# WiFi_UART_Board_R1.net
KiCad netlist of a schematic drawn in EAGLE
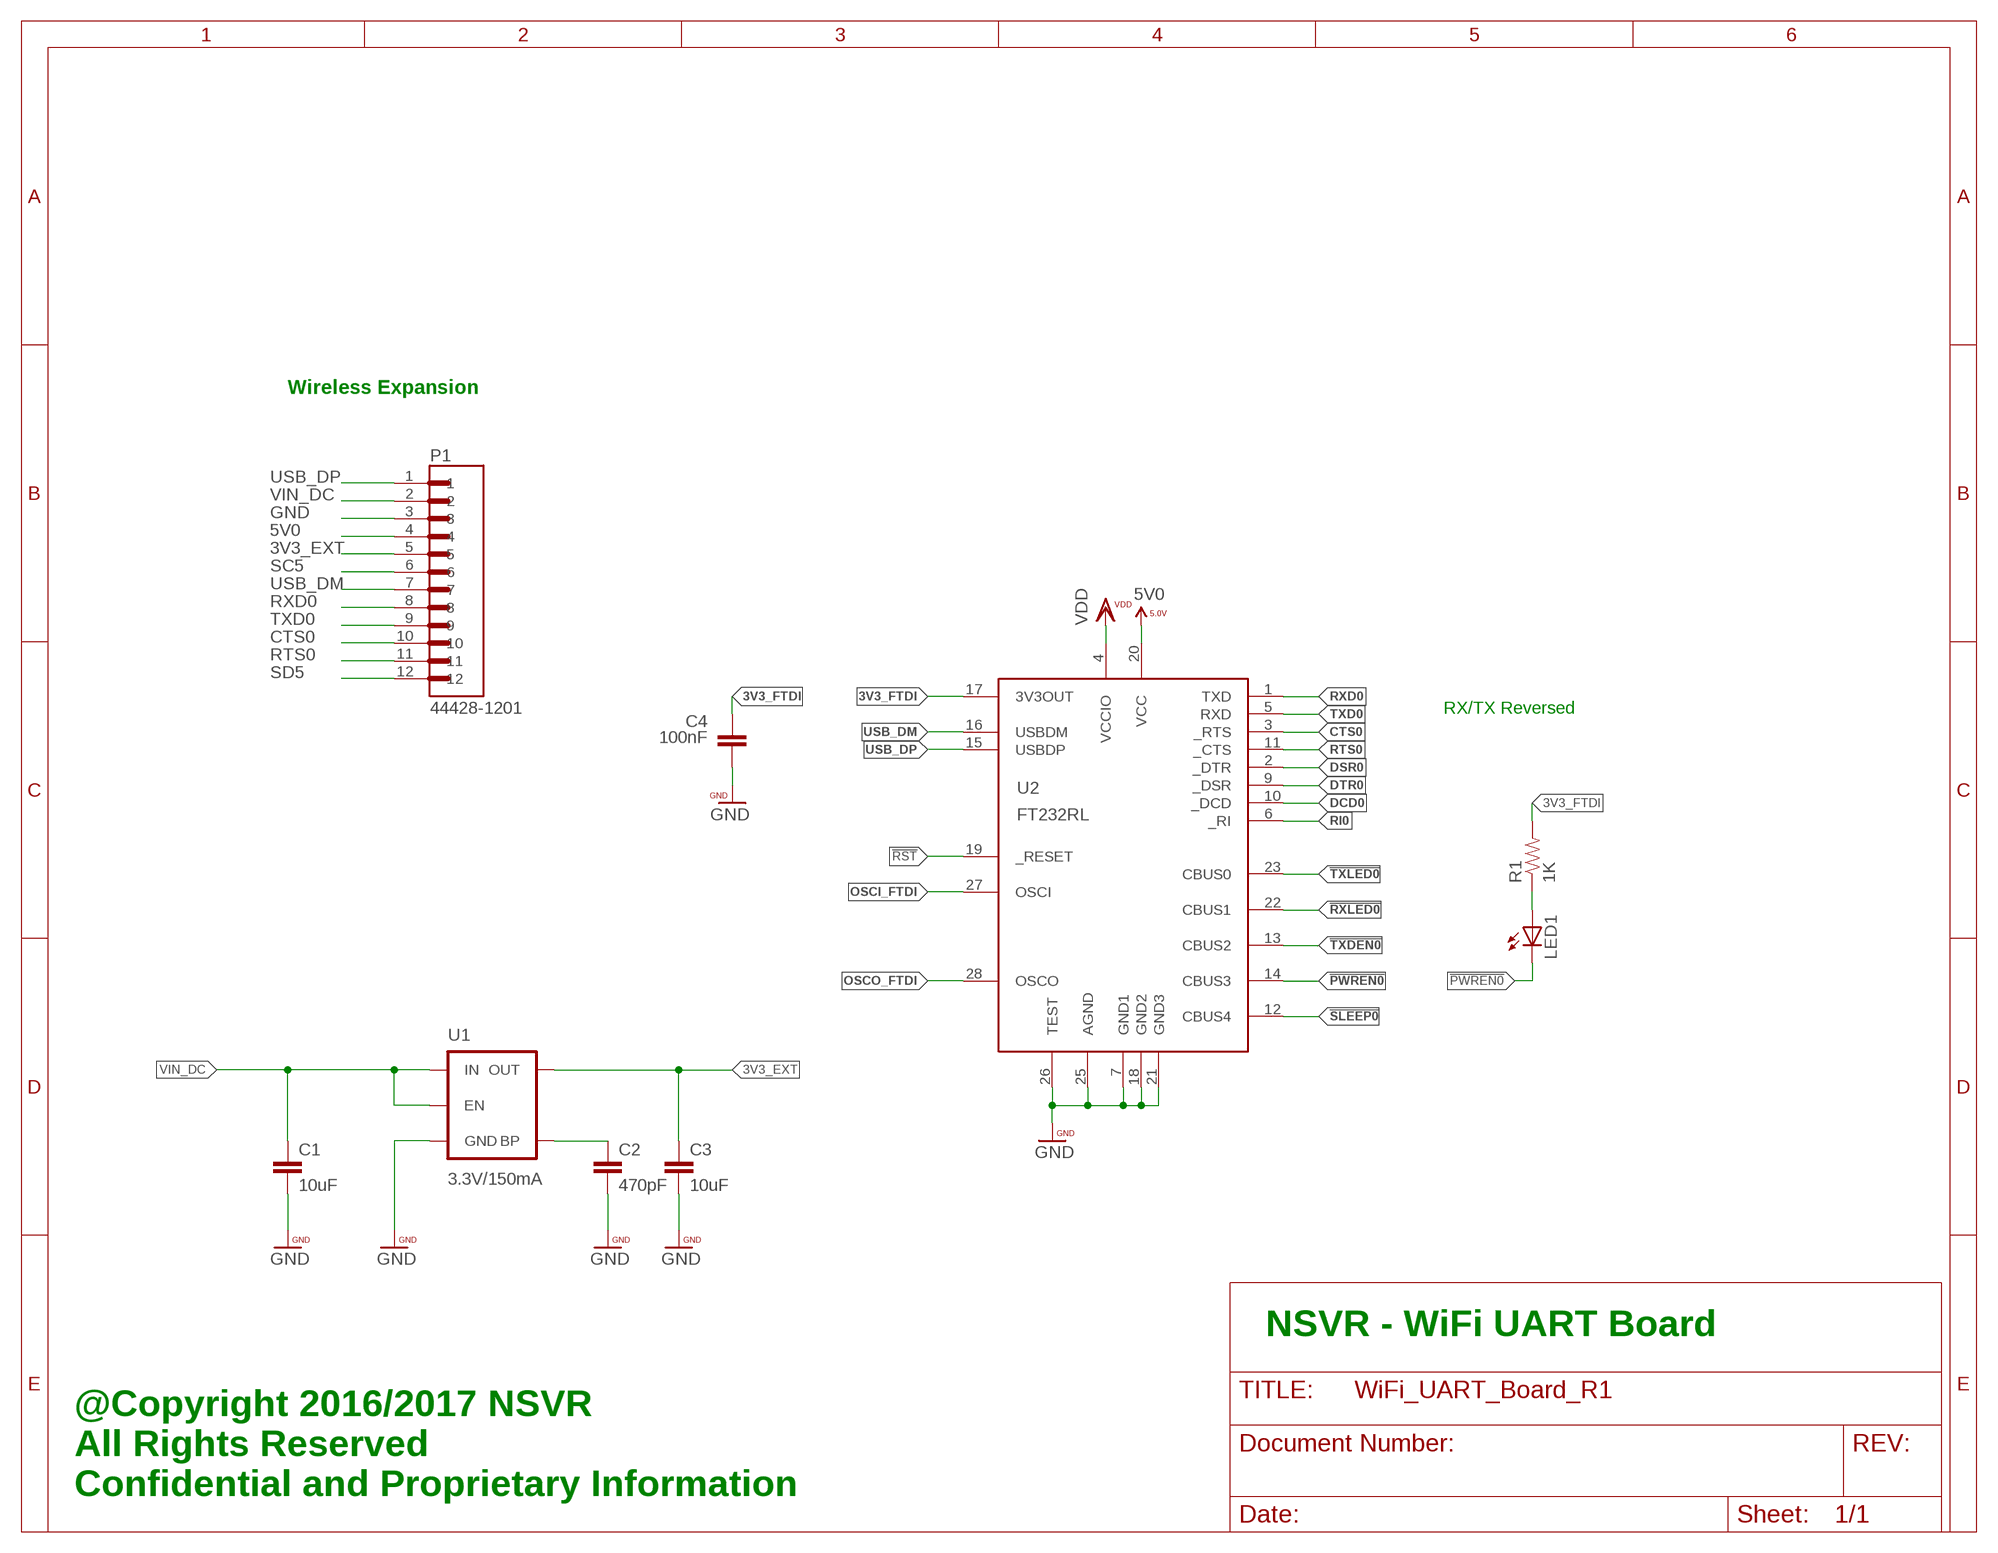
[diagram p0: schematic, sheet 1]

(export (version "E")
  (design (tool "Eeschema 10.0.6"))
  (components
    (comp (ref "C1")
      (value "10uF")
      (footprint "eagle-import:0603-CAP")
      (libsource (lib "eagle-import") (part "CAP0603-CAP"))
    )
    (comp (ref "C2")
      (value "470pF")
      (footprint "eagle-import:0402-CAP")
      (libsource (lib "eagle-import") (part "CAP0402-CAP"))
    )
    (comp (ref "C3")
      (value "10uF")
      (footprint "eagle-import:0603-CAP")
      (libsource (lib "eagle-import") (part "CAP0603-CAP"))
    )
    (comp (ref "C4")
      (value "100nF")
      (footprint "eagle-import:0402-CAP")
      (libsource (lib "eagle-import") (part "CAP0402-CAP"))
    )
    (comp (ref "LED1")
      (value "LEDCHIP-LED0603")
      (footprint "eagle-import:CHIP-LED0603")
      (libsource (lib "eagle-import") (part "LEDCHIP-LED0603"))
    )
    (comp (ref "P1")
      (value "44428-1201")
      (footprint "eagle-import:MOLEX_44428-1201")
      (fields (field (name "MF") "Molex"))
      (libsource (lib "eagle-import") (part "44428-1201"))
    )
    (comp (ref "R1")
      (value "1K")
      (footprint "eagle-import:EIA-0402")
      (libsource (lib "eagle-import") (part "RESISTOR0402-TYP"))
    )
    (comp (ref "U1")
      (value "3.3V/150mA")
      (footprint "eagle-import:SOT23-5")
      (libsource (lib "eagle-import") (part "V_REG_MIC52053.3V"))
    )
    (comp (ref "U2")
      (value "FT232RL")
      (footprint "eagle-import:SSOP28DB")
      (libsource (lib "eagle-import") (part "FT232RL"))
    )
  )
  (nets
    (net (code "1") (name "/SC5") (class "Default")
      (node (ref "P1") (pin "6") (pinfunction "6_6") (pintype "passive"))
    )
    (net (code "2") (name "/SD5") (class "Default")
      (node (ref "P1") (pin "12") (pinfunction "12_12") (pintype "passive"))
    )
    (net (code "3") (name "/~{PWREN0}") (class "Default")
      (node (ref "LED1") (pin "C") (pinfunction "C_C") (pintype "passive"))
      (node (ref "U2") (pin "14") (pinfunction "CBUS3_14") (pintype "bidirectional"))
    )
    (net (code "4") (name "/~{RST}") (class "Default")
      (node (ref "U2") (pin "19") (pinfunction "_RESET_19") (pintype "input"))
    )
    (net (code "5") (name "/~{RXLED0}") (class "Default")
      (node (ref "U2") (pin "22") (pinfunction "CBUS1_22") (pintype "bidirectional"))
    )
    (net (code "6") (name "/~{SLEEP0}") (class "Default")
      (node (ref "U2") (pin "12") (pinfunction "CBUS4_12") (pintype "bidirectional"))
    )
    (net (code "7") (name "/~{TXDEN0}") (class "Default")
      (node (ref "U2") (pin "13") (pinfunction "CBUS2_13") (pintype "bidirectional"))
    )
    (net (code "8") (name "/~{TXLED0}") (class "Default")
      (node (ref "U2") (pin "23") (pinfunction "CBUS0_23") (pintype "bidirectional"))
    )
    (net (code "9") (name "3V3_EXT") (class "Default")
      (node (ref "C3") (pin "1") (pinfunction "1_1") (pintype "passive"))
      (node (ref "P1") (pin "5") (pinfunction "5_5") (pintype "passive"))
      (node (ref "U1") (pin "5") (pinfunction "OUT_5") (pintype "passive"))
    )
    (net (code "10") (name "3V3_FTDI") (class "Default")
      (node (ref "C4") (pin "1") (pinfunction "1_1") (pintype "passive"))
      (node (ref "R1") (pin "2") (pinfunction "2_2") (pintype "passive"))
      (node (ref "U2") (pin "17") (pinfunction "3V3OUT_17") (pintype "output"))
    )
    (net (code "11") (name "5V0") (class "Default")
      (node (ref "P1") (pin "4") (pinfunction "4_4") (pintype "passive"))
      (node (ref "U2") (pin "20") (pinfunction "VCC_20") (pintype "power_in"))
    )
    (net (code "12") (name "CTS0") (class "Default")
      (node (ref "P1") (pin "10") (pinfunction "10_10") (pintype "passive"))
      (node (ref "U2") (pin "3") (pinfunction "_RTS_3") (pintype "output"))
    )
    (net (code "13") (name "DCD0") (class "Default")
      (node (ref "U2") (pin "10") (pinfunction "_DCD_10") (pintype "input"))
    )
    (net (code "14") (name "DSR0") (class "Default")
      (node (ref "U2") (pin "2") (pinfunction "_DTR_2") (pintype "output"))
    )
    (net (code "15") (name "DTR0") (class "Default")
      (node (ref "U2") (pin "9") (pinfunction "_DSR_9") (pintype "input"))
    )
    (net (code "16") (name "GND") (class "Default")
      (node (ref "C1") (pin "2") (pinfunction "2_2") (pintype "passive"))
      (node (ref "C2") (pin "2") (pinfunction "2_2") (pintype "passive"))
      (node (ref "C3") (pin "2") (pinfunction "2_2") (pintype "passive"))
      (node (ref "C4") (pin "2") (pinfunction "2_2") (pintype "passive"))
      (node (ref "P1") (pin "3") (pinfunction "3_3") (pintype "passive"))
      (node (ref "U1") (pin "2") (pinfunction "GND_2") (pintype "input"))
      (node (ref "U2") (pin "18") (pinfunction "GND2_18") (pintype "power_in"))
      (node (ref "U2") (pin "21") (pinfunction "GND3_21") (pintype "power_in"))
      (node (ref "U2") (pin "25") (pinfunction "AGND_25") (pintype "power_in"))
      (node (ref "U2") (pin "26") (pinfunction "TEST_26") (pintype "input"))
      (node (ref "U2") (pin "7") (pinfunction "GND1_7") (pintype "power_in"))
    )
    (net (code "17") (name "Net-(LED1-PadA)") (class "Default")
      (node (ref "LED1") (pin "A") (pinfunction "A_A") (pintype "passive"))
      (node (ref "R1") (pin "1") (pinfunction "1_1") (pintype "passive"))
    )
    (net (code "18") (name "Net-(U1-BP)") (class "Default")
      (node (ref "C2") (pin "1") (pinfunction "1_1") (pintype "passive"))
      (node (ref "U1") (pin "4") (pinfunction "BP_4") (pintype "input"))
    )
    (net (code "19") (name "OSCI_FTDI") (class "Default")
      (node (ref "U2") (pin "27") (pinfunction "OSCI_27") (pintype "input"))
    )
    (net (code "20") (name "OSCO_FTDI") (class "Default")
      (node (ref "U2") (pin "28") (pinfunction "OSCO_28") (pintype "output"))
    )
    (net (code "21") (name "RI0") (class "Default")
      (node (ref "U2") (pin "6") (pinfunction "_RI_6") (pintype "input"))
    )
    (net (code "22") (name "RTS0") (class "Default")
      (node (ref "P1") (pin "11") (pinfunction "11_11") (pintype "passive"))
      (node (ref "U2") (pin "11") (pinfunction "_CTS_11") (pintype "input"))
    )
    (net (code "23") (name "RXD0") (class "Default")
      (node (ref "P1") (pin "8") (pinfunction "8_8") (pintype "passive"))
      (node (ref "U2") (pin "1") (pinfunction "TXD_1") (pintype "output"))
    )
    (net (code "24") (name "TXD0") (class "Default")
      (node (ref "P1") (pin "9") (pinfunction "9_9") (pintype "passive"))
      (node (ref "U2") (pin "5") (pinfunction "RXD_5") (pintype "input"))
    )
    (net (code "25") (name "USB_DM") (class "Default")
      (node (ref "P1") (pin "7") (pinfunction "7_7") (pintype "passive"))
      (node (ref "U2") (pin "16") (pinfunction "USBDM_16") (pintype "bidirectional"))
    )
    (net (code "26") (name "USB_DP") (class "Default")
      (node (ref "P1") (pin "1") (pinfunction "1_1") (pintype "passive"))
      (node (ref "U2") (pin "15") (pinfunction "USBDP_15") (pintype "bidirectional"))
    )
    (net (code "27") (name "VDD") (class "Default")
      (node (ref "U2") (pin "4") (pinfunction "VCCIO_4") (pintype "power_in"))
    )
    (net (code "28") (name "VIN_DC") (class "Default")
      (node (ref "C1") (pin "1") (pinfunction "1_1") (pintype "passive"))
      (node (ref "P1") (pin "2") (pinfunction "2_2") (pintype "passive"))
      (node (ref "U1") (pin "1") (pinfunction "IN_1") (pintype "input"))
      (node (ref "U1") (pin "3") (pinfunction "EN_3") (pintype "input"))
    )
  )
)
